# Peripherals_-_Servos.net
KiCad netlist of a schematic drawn in Altium Designer
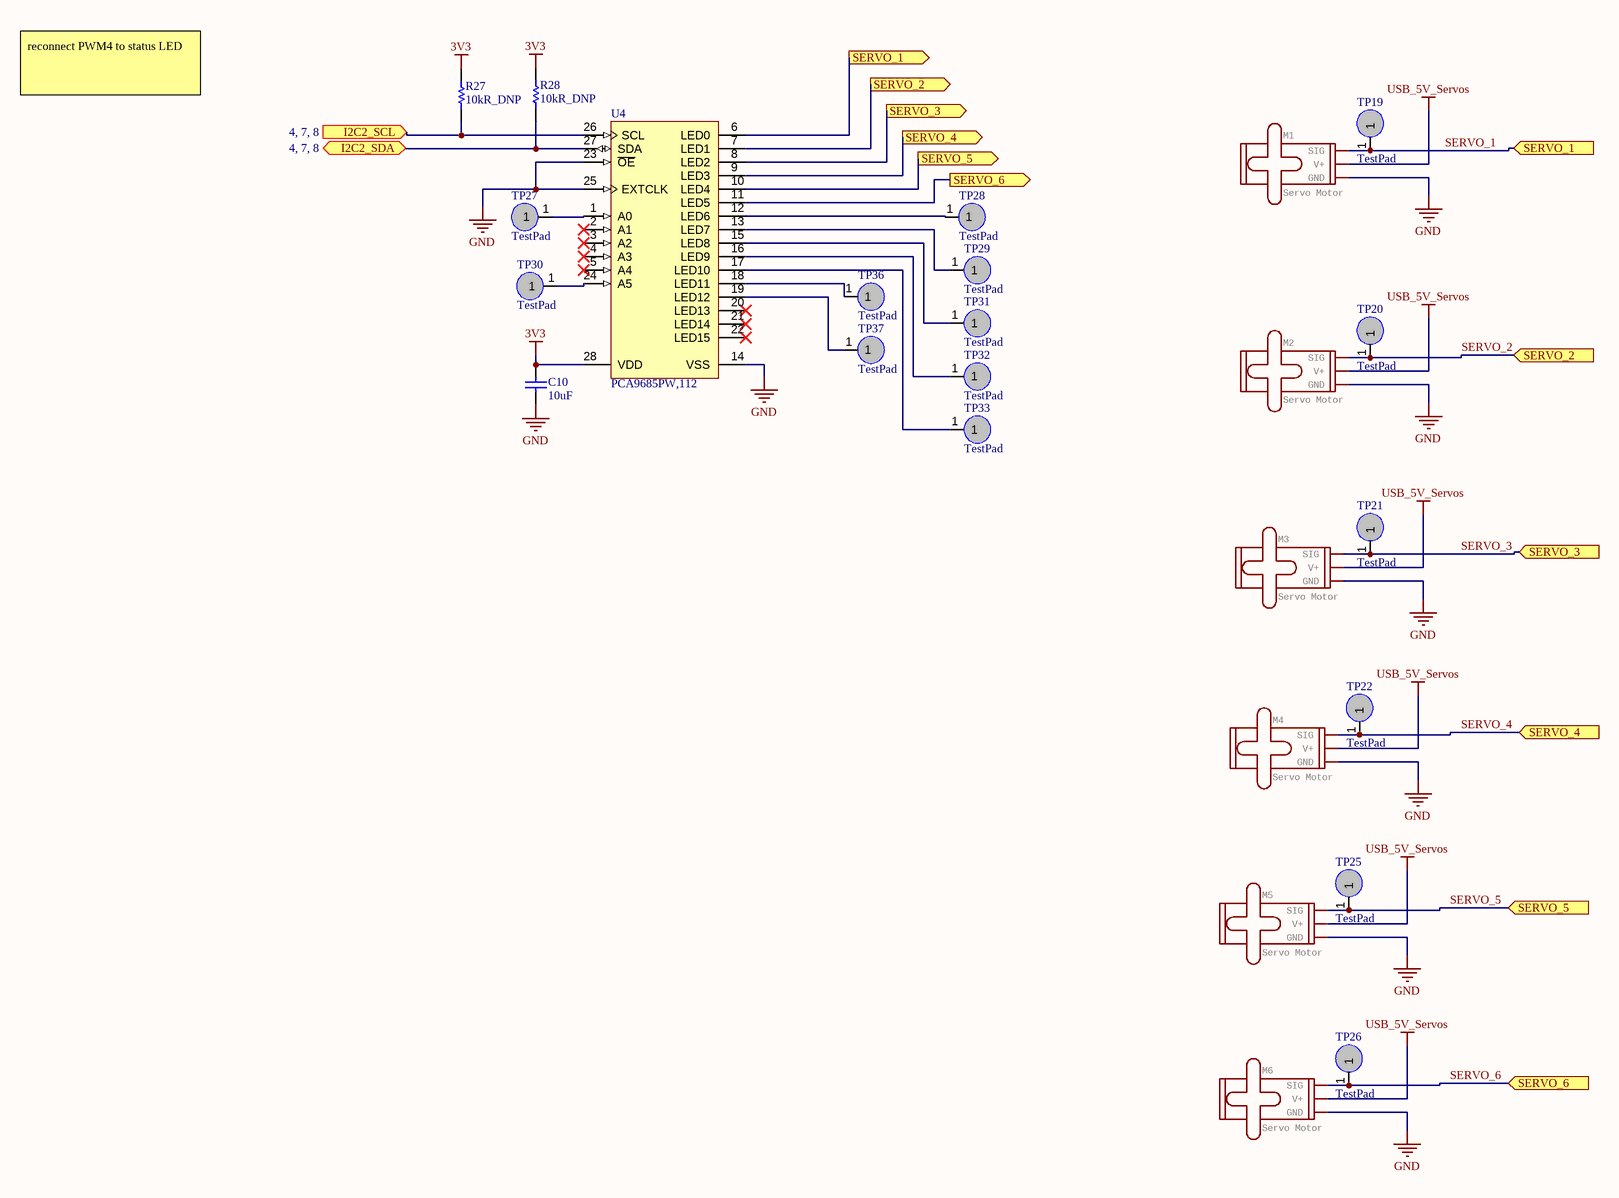
[diagram p0: Peripherals - Servos.SchDoc]

(export (version "E")
  (design (tool "Eeschema 10.0.6"))
  (components
    (comp (ref "C10")
      (value "10uF")
      (footprint "CAPC2013X145X20ML20")
      (fields
        (field (name "MANUFACTURER") "TDK")
        (field (name "TOLERANCE") "±10%")
        (field (name "PCN PART NUMBER") "MLCCPartNumberChange30/Nov/2012")
      )
      (libsource (lib "Altium Content Vault") (part "CAP-NP-2"))
    )
    (comp (ref "M1")
      (value "Servo Motor")
      (footprint "1X03")
      (libsource (lib "SparkFun-Electromechanical.Library") (part "SERVO"))
    )
    (comp (ref "M2")
      (value "Servo Motor")
      (footprint "1X03")
      (libsource (lib "SparkFun-Electromechanical.Library") (part "SERVO"))
    )
    (comp (ref "M3")
      (value "Servo Motor")
      (footprint "1X03")
      (libsource (lib "SparkFun-Electromechanical.Library") (part "SERVO"))
    )
    (comp (ref "M4")
      (value "Servo Motor")
      (footprint "1X03")
      (libsource (lib "SparkFun-Electromechanical.Library") (part "SERVO"))
    )
    (comp (ref "M5")
      (value "Servo Motor")
      (footprint "1X03")
      (libsource (lib "SparkFun-Electromechanical.Library") (part "SERVO"))
    )
    (comp (ref "M6")
      (value "Servo Motor")
      (footprint "1X03")
      (libsource (lib "SparkFun-Electromechanical.Library") (part "SERVO"))
    )
    (comp (ref "R27")
      (value "10kR_DNP")
      (footprint "RESC2013X60X35NL10T20")
      (fields (field (name "MANUFACTURER") "Yageo"))
      (libsource (lib "Altium Content Vault") (part "RES-2"))
    )
    (comp (ref "R28")
      (value "10kR_DNP")
      (footprint "RESC2013X60X35NL10T20")
      (fields (field (name "MANUFACTURER") "Yageo"))
      (libsource (lib "Altium Content Vault") (part "RES-2"))
    )
    (comp (ref "TP19")
      (value "TestPad")
      (footprint "TestPad50mil")
      (libsource (lib "SchemSymbolsGoogle") (part "TestPad"))
    )
    (comp (ref "TP20")
      (value "TestPad")
      (footprint "TestPad50mil")
      (libsource (lib "SchemSymbolsGoogle") (part "TestPad"))
    )
    (comp (ref "TP21")
      (value "TestPad")
      (footprint "TestPad50mil")
      (libsource (lib "SchemSymbolsGoogle") (part "TestPad"))
    )
    (comp (ref "TP22")
      (value "TestPad")
      (footprint "TestPad50mil")
      (libsource (lib "SchemSymbolsGoogle") (part "TestPad"))
    )
    (comp (ref "TP25")
      (value "TestPad")
      (footprint "TestPad50mil")
      (libsource (lib "SchemSymbolsGoogle") (part "TestPad"))
    )
    (comp (ref "TP26")
      (value "TestPad")
      (footprint "TestPad50mil")
      (libsource (lib "SchemSymbolsGoogle") (part "TestPad"))
    )
    (comp (ref "TP27")
      (value "TestPad")
      (footprint "TestPad50mil")
      (libsource (lib "SchemSymbolsGoogle") (part "TestPad"))
    )
    (comp (ref "TP28")
      (value "TestPad")
      (footprint "TestPad50mil")
      (libsource (lib "SchemSymbolsGoogle") (part "TestPad"))
    )
    (comp (ref "TP29")
      (value "TestPad")
      (footprint "TestPad50mil")
      (libsource (lib "SchemSymbolsGoogle") (part "TestPad"))
    )
    (comp (ref "TP30")
      (value "TestPad")
      (footprint "TestPad50mil")
      (libsource (lib "SchemSymbolsGoogle") (part "TestPad"))
    )
    (comp (ref "TP31")
      (value "TestPad")
      (footprint "TestPad50mil")
      (libsource (lib "SchemSymbolsGoogle") (part "TestPad"))
    )
    (comp (ref "TP32")
      (value "TestPad")
      (footprint "TestPad50mil")
      (libsource (lib "SchemSymbolsGoogle") (part "TestPad"))
    )
    (comp (ref "TP33")
      (value "TestPad")
      (footprint "TestPad50mil")
      (libsource (lib "SchemSymbolsGoogle") (part "TestPad"))
    )
    (comp (ref "TP36")
      (value "TestPad")
      (footprint "TestPad50mil")
      (libsource (lib "SchemSymbolsGoogle") (part "TestPad"))
    )
    (comp (ref "TP37")
      (value "TestPad")
      (footprint "TestPad50mil")
      (libsource (lib "SchemSymbolsGoogle") (part "TestPad"))
    )
    (comp (ref "U4")
      (value "PCA9685PW,112")
      (footprint "SOT361-1_V")
      (fields (field (name "PARTNUMBER") "PCA9685"))
      (libsource (lib "Altium Content Vault") (part "NXP-PCA9685-SOT361-1"))
    )
  )
  (nets
    (net (code "1") (name "/I2C2_SCL") (class "Default")
      (node (ref "R27") (pin "2") (pinfunction "2_2") (pintype "passive"))
      (node (ref "U4") (pin "26") (pinfunction "SCL_26") (pintype "input"))
    )
    (net (code "2") (name "/I2C2_SDA") (class "Default")
      (node (ref "R28") (pin "2") (pinfunction "2_2") (pintype "passive"))
      (node (ref "U4") (pin "27") (pinfunction "SDA_27") (pintype "bidirectional"))
    )
    (net (code "3") (name "/SERVO_1") (class "Default")
      (node (ref "M1") (pin "1") (pinfunction "SIG_1") (pintype "bidirectional"))
      (node (ref "TP19") (pin "1") (pinfunction "1_1") (pintype "passive"))
      (node (ref "U4") (pin "6") (pinfunction "LED0_6") (pintype "tri_state"))
    )
    (net (code "4") (name "/SERVO_2") (class "Default")
      (node (ref "M2") (pin "1") (pinfunction "SIG_1") (pintype "bidirectional"))
      (node (ref "TP20") (pin "1") (pinfunction "1_1") (pintype "passive"))
      (node (ref "U4") (pin "7") (pinfunction "LED1_7") (pintype "tri_state"))
    )
    (net (code "5") (name "/SERVO_3") (class "Default")
      (node (ref "M3") (pin "1") (pinfunction "SIG_1") (pintype "bidirectional"))
      (node (ref "TP21") (pin "1") (pinfunction "1_1") (pintype "passive"))
      (node (ref "U4") (pin "8") (pinfunction "LED2_8") (pintype "tri_state"))
    )
    (net (code "6") (name "/SERVO_4") (class "Default")
      (node (ref "M4") (pin "1") (pinfunction "SIG_1") (pintype "bidirectional"))
      (node (ref "TP22") (pin "1") (pinfunction "1_1") (pintype "passive"))
      (node (ref "U4") (pin "9") (pinfunction "LED3_9") (pintype "tri_state"))
    )
    (net (code "7") (name "/SERVO_5") (class "Default")
      (node (ref "M5") (pin "1") (pinfunction "SIG_1") (pintype "bidirectional"))
      (node (ref "TP25") (pin "1") (pinfunction "1_1") (pintype "passive"))
      (node (ref "U4") (pin "10") (pinfunction "LED4_10") (pintype "tri_state"))
    )
    (net (code "8") (name "/SERVO_6") (class "Default")
      (node (ref "M6") (pin "1") (pinfunction "SIG_1") (pintype "bidirectional"))
      (node (ref "TP26") (pin "1") (pinfunction "1_1") (pintype "passive"))
      (node (ref "U4") (pin "11") (pinfunction "LED5_11") (pintype "tri_state"))
    )
    (net (code "9") (name "3V3") (class "Default")
      (node (ref "C10") (pin "2") (pinfunction "2_2") (pintype "passive"))
      (node (ref "R27") (pin "1") (pinfunction "1_1") (pintype "passive"))
      (node (ref "R28") (pin "1") (pinfunction "1_1") (pintype "passive"))
      (node (ref "U4") (pin "28") (pinfunction "VDD_28") (pintype "power_in"))
    )
    (net (code "10") (name "GND") (class "Default")
      (node (ref "C10") (pin "1") (pinfunction "1_1") (pintype "passive"))
      (node (ref "M1") (pin "3") (pinfunction "GND_3") (pintype "bidirectional"))
      (node (ref "M2") (pin "3") (pinfunction "GND_3") (pintype "bidirectional"))
      (node (ref "M3") (pin "3") (pinfunction "GND_3") (pintype "bidirectional"))
      (node (ref "M4") (pin "3") (pinfunction "GND_3") (pintype "bidirectional"))
      (node (ref "M5") (pin "3") (pinfunction "GND_3") (pintype "bidirectional"))
      (node (ref "M6") (pin "3") (pinfunction "GND_3") (pintype "bidirectional"))
      (node (ref "U4") (pin "14") (pinfunction "VSS_14") (pintype "power_in"))
      (node (ref "U4") (pin "23") (pinfunction "~{OE}_23") (pintype "input"))
      (node (ref "U4") (pin "25") (pinfunction "EXTCLK_25") (pintype "input"))
    )
    (net (code "11") (name "Net-(U4-A0)") (class "Default")
      (node (ref "TP27") (pin "1") (pinfunction "1_1") (pintype "passive"))
      (node (ref "U4") (pin "1") (pinfunction "A0_1") (pintype "input"))
    )
    (net (code "12") (name "Net-(U4-A5)") (class "Default")
      (node (ref "TP30") (pin "1") (pinfunction "1_1") (pintype "passive"))
      (node (ref "U4") (pin "24") (pinfunction "A5_24") (pintype "input"))
    )
    (net (code "13") (name "Net-(U4-LED6)") (class "Default")
      (node (ref "TP28") (pin "1") (pinfunction "1_1") (pintype "passive"))
      (node (ref "U4") (pin "12") (pinfunction "LED6_12") (pintype "tri_state"))
    )
    (net (code "14") (name "Net-(U4-LED7)") (class "Default")
      (node (ref "TP29") (pin "1") (pinfunction "1_1") (pintype "passive"))
      (node (ref "U4") (pin "13") (pinfunction "LED7_13") (pintype "tri_state"))
    )
    (net (code "15") (name "Net-(U4-LED8)") (class "Default")
      (node (ref "TP31") (pin "1") (pinfunction "1_1") (pintype "passive"))
      (node (ref "U4") (pin "15") (pinfunction "LED8_15") (pintype "tri_state"))
    )
    (net (code "16") (name "Net-(U4-LED9)") (class "Default")
      (node (ref "TP32") (pin "1") (pinfunction "1_1") (pintype "passive"))
      (node (ref "U4") (pin "16") (pinfunction "LED9_16") (pintype "tri_state"))
    )
    (net (code "17") (name "Net-(U4-LED10)") (class "Default")
      (node (ref "TP33") (pin "1") (pinfunction "1_1") (pintype "passive"))
      (node (ref "U4") (pin "17") (pinfunction "LED10_17") (pintype "tri_state"))
    )
    (net (code "18") (name "Net-(U4-LED11)") (class "Default")
      (node (ref "TP36") (pin "1") (pinfunction "1_1") (pintype "passive"))
      (node (ref "U4") (pin "18") (pinfunction "LED11_18") (pintype "tri_state"))
    )
    (net (code "19") (name "Net-(U4-LED12)") (class "Default")
      (node (ref "TP37") (pin "1") (pinfunction "1_1") (pintype "passive"))
      (node (ref "U4") (pin "19") (pinfunction "LED12_19") (pintype "tri_state"))
    )
    (net (code "20") (name "USB_5V_Servos") (class "Default")
      (node (ref "M1") (pin "2") (pinfunction "V+_2") (pintype "bidirectional"))
      (node (ref "M2") (pin "2") (pinfunction "V+_2") (pintype "bidirectional"))
      (node (ref "M3") (pin "2") (pinfunction "V+_2") (pintype "bidirectional"))
      (node (ref "M4") (pin "2") (pinfunction "V+_2") (pintype "bidirectional"))
      (node (ref "M5") (pin "2") (pinfunction "V+_2") (pintype "bidirectional"))
      (node (ref "M6") (pin "2") (pinfunction "V+_2") (pintype "bidirectional"))
    )
    (net (code "21") (name "unconnected-(U4-A1-Pad2)") (class "Default")
      (node (ref "U4") (pin "2") (pinfunction "A1_2") (pintype "input+no_connect"))
    )
    (net (code "22") (name "unconnected-(U4-A2-Pad3)") (class "Default")
      (node (ref "U4") (pin "3") (pinfunction "A2_3") (pintype "input+no_connect"))
    )
    (net (code "23") (name "unconnected-(U4-A3-Pad4)") (class "Default")
      (node (ref "U4") (pin "4") (pinfunction "A3_4") (pintype "input+no_connect"))
    )
    (net (code "24") (name "unconnected-(U4-A4-Pad5)") (class "Default")
      (node (ref "U4") (pin "5") (pinfunction "A4_5") (pintype "input+no_connect"))
    )
    (net (code "25") (name "unconnected-(U4-LED13-Pad20)") (class "Default")
      (node (ref "U4") (pin "20") (pinfunction "LED13_20") (pintype "tri_state+no_connect"))
    )
    (net (code "26") (name "unconnected-(U4-LED14-Pad21)") (class "Default")
      (node (ref "U4") (pin "21") (pinfunction "LED14_21") (pintype "tri_state+no_connect"))
    )
    (net (code "27") (name "unconnected-(U4-LED15-Pad22)") (class "Default")
      (node (ref "U4") (pin "22") (pinfunction "LED15_22") (pintype "tri_state+no_connect"))
    )
  )
)
